# board.net
KiCad netlist of a schematic drawn in EAGLE
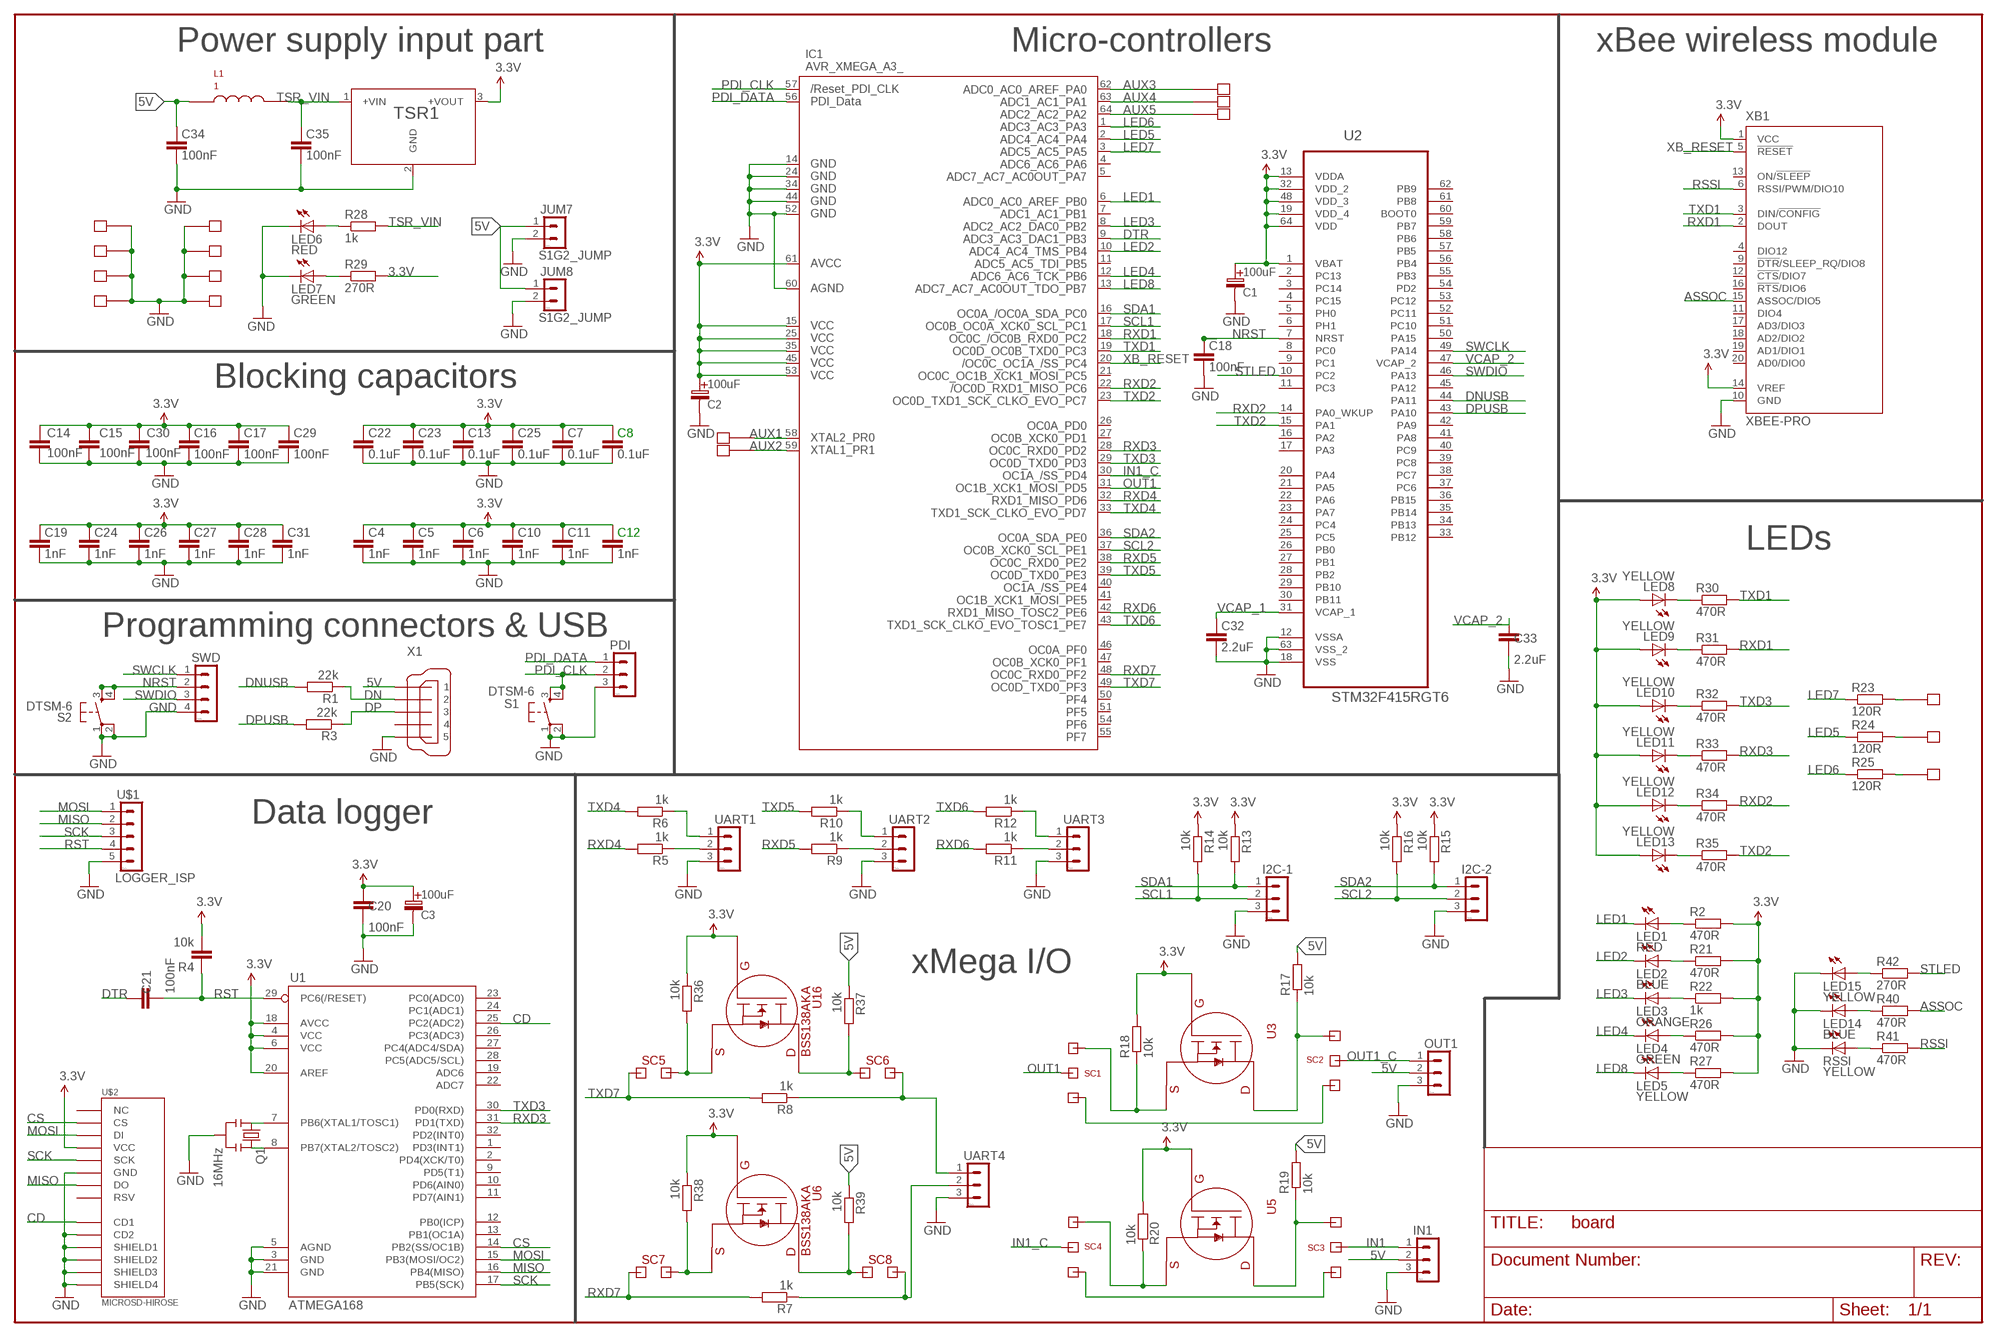
[diagram p0: schematic, sheet 1]

(export (version "E")
  (design (tool "Eeschema 10.0.6"))
  (components
    (comp (ref "AUX1")
      (value "PIN")
      (footprint "eagle-import:PIN")
      (libsource (lib "eagle-import") (part "PIN"))
    )
    (comp (ref "AUX2")
      (value "PIN")
      (footprint "eagle-import:PIN")
      (libsource (lib "eagle-import") (part "PIN"))
    )
    (comp (ref "AUX3")
      (value "PIN")
      (footprint "eagle-import:PIN")
      (libsource (lib "eagle-import") (part "PIN"))
    )
    (comp (ref "AUX4")
      (value "PIN")
      (footprint "eagle-import:PIN")
      (libsource (lib "eagle-import") (part "PIN"))
    )
    (comp (ref "AUX5")
      (value "PIN")
      (footprint "eagle-import:PIN")
      (libsource (lib "eagle-import") (part "PIN"))
    )
    (comp (ref "C1")
      (value "100uF")
      (footprint "eagle-import:B")
      (libsource (lib "eagle-import") (part "CAPACITOR_TANTAL"))
    )
    (comp (ref "C2")
      (value "100uF")
      (footprint "eagle-import:B")
      (libsource (lib "eagle-import") (part "CAPACITOR_TANTAL"))
    )
    (comp (ref "C3")
      (value "100uF")
      (footprint "eagle-import:B")
      (libsource (lib "eagle-import") (part "CAPACITOR_TANTAL"))
    )
    (comp (ref "C4")
      (value "1nF")
      (footprint "eagle-import:C0805")
      (libsource (lib "eagle-import") (part "C-EUC0805"))
    )
    (comp (ref "C5")
      (value "1nF")
      (footprint "eagle-import:C0805")
      (libsource (lib "eagle-import") (part "C-EUC0805"))
    )
    (comp (ref "C6")
      (value "1nF")
      (footprint "eagle-import:C0805")
      (libsource (lib "eagle-import") (part "C-EUC0805"))
    )
    (comp (ref "C7")
      (value "0.1uF")
      (footprint "eagle-import:C0805")
      (libsource (lib "eagle-import") (part "C-EUC0805"))
    )
    (comp (ref "C8")
      (value "0.1uF")
      (footprint "eagle-import:C0805")
      (libsource (lib "eagle-import") (part "C-EUC0805"))
    )
    (comp (ref "C10")
      (value "1nF")
      (footprint "eagle-import:C0805")
      (libsource (lib "eagle-import") (part "C-EUC0805"))
    )
    (comp (ref "C11")
      (value "1nF")
      (footprint "eagle-import:C0805")
      (libsource (lib "eagle-import") (part "C-EUC0805"))
    )
    (comp (ref "C12")
      (value "1nF")
      (footprint "eagle-import:C0805")
      (libsource (lib "eagle-import") (part "C-EUC0805"))
    )
    (comp (ref "C13")
      (value "0.1uF")
      (footprint "eagle-import:C0805")
      (libsource (lib "eagle-import") (part "C-EUC0805"))
    )
    (comp (ref "C14")
      (value "100nF")
      (footprint "eagle-import:C0805")
      (libsource (lib "eagle-import") (part "C-EUC0805"))
    )
    (comp (ref "C15")
      (value "100nF")
      (footprint "eagle-import:C0805")
      (libsource (lib "eagle-import") (part "C-EUC0805"))
    )
    (comp (ref "C16")
      (value "100nF")
      (footprint "eagle-import:C0805")
      (libsource (lib "eagle-import") (part "C-EUC0805"))
    )
    (comp (ref "C17")
      (value "100nF")
      (footprint "eagle-import:C0805")
      (libsource (lib "eagle-import") (part "C-EUC0805"))
    )
    (comp (ref "C18")
      (value "100nF")
      (footprint "eagle-import:C0805")
      (libsource (lib "eagle-import") (part "C-EUC0805"))
    )
    (comp (ref "C19")
      (value "1nF")
      (footprint "eagle-import:C0805")
      (libsource (lib "eagle-import") (part "C-EUC0805"))
    )
    (comp (ref "C20")
      (value "100nF")
      (footprint "eagle-import:C0805")
      (libsource (lib "eagle-import") (part "C-EUC0805"))
    )
    (comp (ref "C21")
      (value "100nF")
      (footprint "eagle-import:C0805")
      (libsource (lib "eagle-import") (part "C-EUC0805"))
    )
    (comp (ref "C22")
      (value "0.1uF")
      (footprint "eagle-import:C0805")
      (libsource (lib "eagle-import") (part "C-EUC0805"))
    )
    (comp (ref "C23")
      (value "0.1uF")
      (footprint "eagle-import:C0805")
      (libsource (lib "eagle-import") (part "C-EUC0805"))
    )
    (comp (ref "C24")
      (value "1nF")
      (footprint "eagle-import:C0805")
      (libsource (lib "eagle-import") (part "C-EUC0805"))
    )
    (comp (ref "C25")
      (value "0.1uF")
      (footprint "eagle-import:C0805")
      (libsource (lib "eagle-import") (part "C-EUC0805"))
    )
    (comp (ref "C26")
      (value "1nF")
      (footprint "eagle-import:C0805")
      (libsource (lib "eagle-import") (part "C-EUC0805"))
    )
    (comp (ref "C27")
      (value "1nF")
      (footprint "eagle-import:C0805")
      (libsource (lib "eagle-import") (part "C-EUC0805"))
    )
    (comp (ref "C28")
      (value "1nF")
      (footprint "eagle-import:C0805")
      (libsource (lib "eagle-import") (part "C-EUC0805"))
    )
    (comp (ref "C29")
      (value "100nF")
      (footprint "eagle-import:C0805")
      (libsource (lib "eagle-import") (part "C-EUC0805"))
    )
    (comp (ref "C30")
      (value "100nF")
      (footprint "eagle-import:C0805")
      (libsource (lib "eagle-import") (part "C-EUC0805"))
    )
    (comp (ref "C31")
      (value "1nF")
      (footprint "eagle-import:C0805")
      (libsource (lib "eagle-import") (part "C-EUC0805"))
    )
    (comp (ref "C32")
      (value "2.2uF")
      (footprint "eagle-import:C0805")
      (libsource (lib "eagle-import") (part "C-EUC0805"))
    )
    (comp (ref "C33")
      (value "2.2uF")
      (footprint "eagle-import:C0805")
      (libsource (lib "eagle-import") (part "C-EUC0805"))
    )
    (comp (ref "C34")
      (value "100nF")
      (footprint "eagle-import:C0805")
      (libsource (lib "eagle-import") (part "C-EUC0805"))
    )
    (comp (ref "C35")
      (value "100nF")
      (footprint "eagle-import:C0805")
      (libsource (lib "eagle-import") (part "C-EUC0805"))
    )
    (comp (ref "I2C-1")
      (value "S1G3_JUMP")
      (footprint "eagle-import:S1G3_JUM")
      (libsource (lib "eagle-import") (part "S1G3_JUMP"))
    )
    (comp (ref "I2C-2")
      (value "S1G3_JUMP")
      (footprint "eagle-import:S1G3_JUM")
      (libsource (lib "eagle-import") (part "S1G3_JUMP"))
    )
    (comp (ref "IC1")
      (value "AVR_XMEGA_A3_")
      (footprint "eagle-import:TQFP64")
      (libsource (lib "eagle-import") (part "AVR_XMEGA_A3_"))
    )
    (comp (ref "IN1")
      (value "S1G3_JUMP")
      (footprint "eagle-import:S1G3_JUM")
      (libsource (lib "eagle-import") (part "S1G3_JUMP"))
    )
    (comp (ref "JUM7")
      (value "S1G2_JUMP")
      (footprint "eagle-import:S1G2_JUM")
      (libsource (lib "eagle-import") (part "S1G2_JUMP"))
    )
    (comp (ref "JUM8")
      (value "S1G2_JUMP")
      (footprint "eagle-import:S1G2_JUM")
      (libsource (lib "eagle-import") (part "S1G2_JUMP"))
    )
    (comp (ref "L1")
      (value "1")
      (footprint "eagle-import:SDR0604")
      (libsource (lib "eagle-import") (part "LSDR0604"))
    )
    (comp (ref "LED1")
      (value "RED")
      (footprint "eagle-import:SML0805")
      (libsource (lib "eagle-import") (part "LEDSML0805"))
    )
    (comp (ref "LED2")
      (value "BLUE")
      (footprint "eagle-import:SML0805")
      (libsource (lib "eagle-import") (part "LEDSML0805"))
    )
    (comp (ref "LED3")
      (value "ORANGE")
      (footprint "eagle-import:SML0805")
      (libsource (lib "eagle-import") (part "LEDSML0805"))
    )
    (comp (ref "LED4")
      (value "GREEN")
      (footprint "eagle-import:SML0805")
      (libsource (lib "eagle-import") (part "LEDSML0805"))
    )
    (comp (ref "LED5")
      (value "YELLOW")
      (footprint "eagle-import:SML0805")
      (libsource (lib "eagle-import") (part "LEDSML0805"))
    )
    (comp (ref "LED6")
      (value "RED")
      (footprint "eagle-import:SML0805")
      (libsource (lib "eagle-import") (part "LEDSML0805"))
    )
    (comp (ref "LED7")
      (value "GREEN")
      (footprint "eagle-import:SML0805")
      (libsource (lib "eagle-import") (part "LEDSML0805"))
    )
    (comp (ref "LED8")
      (value "YELLOW")
      (footprint "eagle-import:SML0805")
      (libsource (lib "eagle-import") (part "LEDSML0805"))
    )
    (comp (ref "LED9")
      (value "YELLOW")
      (footprint "eagle-import:SML0805")
      (libsource (lib "eagle-import") (part "LEDSML0805"))
    )
    (comp (ref "LED10")
      (value "YELLOW")
      (footprint "eagle-import:SML0805")
      (libsource (lib "eagle-import") (part "LEDSML0805"))
    )
    (comp (ref "LED11")
      (value "YELLOW")
      (footprint "eagle-import:SML0805")
      (libsource (lib "eagle-import") (part "LEDSML0805"))
    )
    (comp (ref "LED12")
      (value "YELLOW")
      (footprint "eagle-import:SML0805")
      (libsource (lib "eagle-import") (part "LEDSML0805"))
    )
    (comp (ref "LED13")
      (value "YELLOW")
      (footprint "eagle-import:SML0805")
      (libsource (lib "eagle-import") (part "LEDSML0805"))
    )
    (comp (ref "LED14")
      (value "BLUE")
      (footprint "eagle-import:SML0805")
      (libsource (lib "eagle-import") (part "LEDSML0805"))
    )
    (comp (ref "LED15")
      (value "YELLOW")
      (footprint "eagle-import:SML0805")
      (libsource (lib "eagle-import") (part "LEDSML0805"))
    )
    (comp (ref "OUT1")
      (value "S1G3_JUMP")
      (footprint "eagle-import:S1G3_JUM")
      (libsource (lib "eagle-import") (part "S1G3_JUMP"))
    )
    (comp (ref "PDI")
      (value "S1G3_JUMP")
      (footprint "eagle-import:S1G3_JUM")
      (libsource (lib "eagle-import") (part "S1G3_JUMP"))
    )
    (comp (ref "Q1")
      (value "16MHz")
      (footprint "eagle-import:RESONATOR-SMD")
      (libsource (lib "eagle-import") (part "RESONATORSMD"))
    )
    (comp (ref "R1")
      (value "22k")
      (footprint "eagle-import:R0805")
      (libsource (lib "eagle-import") (part "R-EU_R0805"))
    )
    (comp (ref "R2")
      (value "470R")
      (footprint "eagle-import:R0805")
      (libsource (lib "eagle-import") (part "R-EU_R0805"))
    )
    (comp (ref "R3")
      (value "22k")
      (footprint "eagle-import:R0805")
      (libsource (lib "eagle-import") (part "R-EU_R0805"))
    )
    (comp (ref "R4")
      (value "10k")
      (footprint "eagle-import:C0805")
      (libsource (lib "eagle-import") (part "C-EUC0805"))
    )
    (comp (ref "R5")
      (value "1k")
      (footprint "eagle-import:R0805")
      (libsource (lib "eagle-import") (part "R-EU_R0805"))
    )
    (comp (ref "R6")
      (value "1k")
      (footprint "eagle-import:R0805")
      (libsource (lib "eagle-import") (part "R-EU_R0805"))
    )
    (comp (ref "R7")
      (value "1k")
      (footprint "eagle-import:R0805")
      (libsource (lib "eagle-import") (part "R-EU_R0805"))
    )
    (comp (ref "R8")
      (value "1k")
      (footprint "eagle-import:R0805")
      (libsource (lib "eagle-import") (part "R-EU_R0805"))
    )
    (comp (ref "R9")
      (value "1k")
      (footprint "eagle-import:R0805")
      (libsource (lib "eagle-import") (part "R-EU_R0805"))
    )
    (comp (ref "R10")
      (value "1k")
      (footprint "eagle-import:R0805")
      (libsource (lib "eagle-import") (part "R-EU_R0805"))
    )
    (comp (ref "R11")
      (value "1k")
      (footprint "eagle-import:R0805")
      (libsource (lib "eagle-import") (part "R-EU_R0805"))
    )
    (comp (ref "R12")
      (value "1k")
      (footprint "eagle-import:R0805")
      (libsource (lib "eagle-import") (part "R-EU_R0805"))
    )
    (comp (ref "R13")
      (value "10k")
      (footprint "eagle-import:R0805")
      (libsource (lib "eagle-import") (part "R-EU_R0805"))
    )
    (comp (ref "R14")
      (value "10k")
      (footprint "eagle-import:R0805")
      (libsource (lib "eagle-import") (part "R-EU_R0805"))
    )
    (comp (ref "R15")
      (value "10k")
      (footprint "eagle-import:R0805")
      (libsource (lib "eagle-import") (part "R-EU_R0805"))
    )
    (comp (ref "R16")
      (value "10k")
      (footprint "eagle-import:R0805")
      (libsource (lib "eagle-import") (part "R-EU_R0805"))
    )
    (comp (ref "R17")
      (value "10k")
      (footprint "eagle-import:R0805")
      (libsource (lib "eagle-import") (part "R-EU_R0805"))
    )
    (comp (ref "R18")
      (value "10k")
      (footprint "eagle-import:R0805")
      (libsource (lib "eagle-import") (part "R-EU_R0805"))
    )
    (comp (ref "R19")
      (value "10k")
      (footprint "eagle-import:R0805")
      (libsource (lib "eagle-import") (part "R-EU_R0805"))
    )
    (comp (ref "R20")
      (value "10k")
      (footprint "eagle-import:R0805")
      (libsource (lib "eagle-import") (part "R-EU_R0805"))
    )
    (comp (ref "R21")
      (value "470R")
      (footprint "eagle-import:R0805")
      (libsource (lib "eagle-import") (part "R-EU_R0805"))
    )
    (comp (ref "R22")
      (value "1k")
      (footprint "eagle-import:R0805")
      (libsource (lib "eagle-import") (part "R-EU_R0805"))
    )
    (comp (ref "R23")
      (value "120R")
      (footprint "eagle-import:R0805")
      (libsource (lib "eagle-import") (part "R-EU_R0805"))
    )
    (comp (ref "R24")
      (value "120R")
      (footprint "eagle-import:R0805")
      (libsource (lib "eagle-import") (part "R-EU_R0805"))
    )
    (comp (ref "R25")
      (value "120R")
      (footprint "eagle-import:R0805")
      (libsource (lib "eagle-import") (part "R-EU_R0805"))
    )
    (comp (ref "R26")
      (value "470R")
      (footprint "eagle-import:R0805")
      (libsource (lib "eagle-import") (part "R-EU_R0805"))
    )
    (comp (ref "R27")
      (value "470R")
      (footprint "eagle-import:R0805")
      (libsource (lib "eagle-import") (part "R-EU_R0805"))
    )
    (comp (ref "R28")
      (value "1k")
      (footprint "eagle-import:R0805")
      (libsource (lib "eagle-import") (part "R-EU_R0805"))
    )
    (comp (ref "R29")
      (value "270R")
      (footprint "eagle-import:R0805")
      (libsource (lib "eagle-import") (part "R-EU_R0805"))
    )
    (comp (ref "R30")
      (value "470R")
      (footprint "eagle-import:R0805")
      (libsource (lib "eagle-import") (part "R-EU_R0805"))
    )
    (comp (ref "R31")
      (value "470R")
      (footprint "eagle-import:R0805")
      (libsource (lib "eagle-import") (part "R-EU_R0805"))
    )
    (comp (ref "R32")
      (value "470R")
      (footprint "eagle-import:R0805")
      (libsource (lib "eagle-import") (part "R-EU_R0805"))
    )
    (comp (ref "R33")
      (value "470R")
      (footprint "eagle-import:R0805")
      (libsource (lib "eagle-import") (part "R-EU_R0805"))
    )
    (comp (ref "R34")
      (value "470R")
      (footprint "eagle-import:R0805")
      (libsource (lib "eagle-import") (part "R-EU_R0805"))
    )
    (comp (ref "R35")
      (value "470R")
      (footprint "eagle-import:R0805")
      (libsource (lib "eagle-import") (part "R-EU_R0805"))
    )
    (comp (ref "R36")
      (value "10k")
      (footprint "eagle-import:R0805")
      (libsource (lib "eagle-import") (part "R-EU_R0805"))
    )
    (comp (ref "R37")
      (value "10k")
      (footprint "eagle-import:R0805")
      (libsource (lib "eagle-import") (part "R-EU_R0805"))
    )
    (comp (ref "R38")
      (value "10k")
      (footprint "eagle-import:R0805")
      (libsource (lib "eagle-import") (part "R-EU_R0805"))
    )
    (comp (ref "R39")
      (value "10k")
      (footprint "eagle-import:R0805")
      (libsource (lib "eagle-import") (part "R-EU_R0805"))
    )
    (comp (ref "R40")
      (value "470R")
      (footprint "eagle-import:R0805")
      (libsource (lib "eagle-import") (part "R-EU_R0805"))
    )
    (comp (ref "R41")
      (value "470R")
      (footprint "eagle-import:R0805")
      (libsource (lib "eagle-import") (part "R-EU_R0805"))
    )
    (comp (ref "R42")
      (value "270R")
      (footprint "eagle-import:R0805")
      (libsource (lib "eagle-import") (part "R-EU_R0805"))
    )
    (comp (ref "RSSI")
      (value "YELLOW")
      (footprint "eagle-import:SML0805")
      (libsource (lib "eagle-import") (part "LEDSML0805"))
    )
    (comp (ref "S1")
      (value "DTSM-6")
      (footprint "eagle-import:DTSM-6")
      (libsource (lib "eagle-import") (part "DTSM-6"))
    )
    (comp (ref "S2")
      (value "DTSM-6")
      (footprint "eagle-import:DTSM-6")
      (libsource (lib "eagle-import") (part "DTSM-6"))
    )
    (comp (ref "SC1")
      (value "SOLDER_SWITCH_ONE")
      (footprint "eagle-import:SOLDER_SWITCH")
      (libsource (lib "eagle-import") (part "SOLDER_SWITCH_ONE"))
    )
    (comp (ref "SC2")
      (value "SOLDER_SWITCH_TWO")
      (footprint "eagle-import:SOLDER_SWITCH")
      (libsource (lib "eagle-import") (part "SOLDER_SWITCH_TWO"))
    )
    (comp (ref "SC3")
      (value "SOLDER_SWITCH_ONE")
      (footprint "eagle-import:SOLDER_SWITCH")
      (libsource (lib "eagle-import") (part "SOLDER_SWITCH_ONE"))
    )
    (comp (ref "SC4")
      (value "SOLDER_SWITCH_TWO")
      (footprint "eagle-import:SOLDER_SWITCH")
      (libsource (lib "eagle-import") (part "SOLDER_SWITCH_TWO"))
    )
    (comp (ref "SC5")
      (value "SOLDER_SWITCH_2")
      (footprint "eagle-import:SOLDER_SWITCH_2")
      (libsource (lib "eagle-import") (part "SOLDER_SWITCH_2"))
    )
    (comp (ref "SC6")
      (value "SOLDER_SWITCH_2")
      (footprint "eagle-import:SOLDER_SWITCH_2")
      (libsource (lib "eagle-import") (part "SOLDER_SWITCH_2"))
    )
    (comp (ref "SC7")
      (value "SOLDER_SWITCH_2")
      (footprint "eagle-import:SOLDER_SWITCH_2")
      (libsource (lib "eagle-import") (part "SOLDER_SWITCH_2"))
    )
    (comp (ref "SC8")
      (value "SOLDER_SWITCH_2")
      (footprint "eagle-import:SOLDER_SWITCH_2")
      (libsource (lib "eagle-import") (part "SOLDER_SWITCH_2"))
    )
    (comp (ref "SWD")
      (value "S1G4_JUMP_SQUARE")
      (footprint "eagle-import:2X02")
      (libsource (lib "eagle-import") (part "S1G4_JUMP_SQUARE"))
    )
    (comp (ref "TSR")
      (value "TSR1")
      (footprint "eagle-import:TSR1")
      (libsource (lib "eagle-import") (part "TSR1"))
    )
    (comp (ref "U$1")
      (value "LOGGER_ISP")
      (footprint "eagle-import:LOGGER_ISP")
      (libsource (lib "eagle-import") (part "LOGGER_ISP"))
    )
    (comp (ref "U$2")
      (value "MICROSD-HIROSE")
      (footprint "eagle-import:MICROSD_HOLDER-HIROSE-DM3AT")
      (libsource (lib "eagle-import") (part "MICROSD-HIROSE"))
    )
    (comp (ref "U$10")
      (value "PIN")
      (footprint "eagle-import:PIN")
      (libsource (lib "eagle-import") (part "PIN"))
    )
    (comp (ref "U$11")
      (value "PIN")
      (footprint "eagle-import:PIN")
      (libsource (lib "eagle-import") (part "PIN"))
    )
    (comp (ref "U$12")
      (value "PIN")
      (footprint "eagle-import:PIN")
      (libsource (lib "eagle-import") (part "PIN"))
    )
    (comp (ref "U$15")
      (value "PIN")
      (footprint "eagle-import:PIN")
      (libsource (lib "eagle-import") (part "PIN"))
    )
    (comp (ref "U$16")
      (value "PIN")
      (footprint "eagle-import:PIN")
      (libsource (lib "eagle-import") (part "PIN"))
    )
    (comp (ref "U$17")
      (value "PIN")
      (footprint "eagle-import:PIN")
      (libsource (lib "eagle-import") (part "PIN"))
    )
    (comp (ref "U$18")
      (value "PIN")
      (footprint "eagle-import:PIN")
      (libsource (lib "eagle-import") (part "PIN"))
    )
    (comp (ref "U$19")
      (value "PIN")
      (footprint "eagle-import:PIN")
      (libsource (lib "eagle-import") (part "PIN"))
    )
    (comp (ref "U$20")
      (value "PIN")
      (footprint "eagle-import:PIN")
      (libsource (lib "eagle-import") (part "PIN"))
    )
    (comp (ref "U$21")
      (value "PIN")
      (footprint "eagle-import:PIN")
      (libsource (lib "eagle-import") (part "PIN"))
    )
    (comp (ref "U$22")
      (value "PIN")
      (footprint "eagle-import:PIN")
      (libsource (lib "eagle-import") (part "PIN"))
    )
    (comp (ref "U1")
      (value "ATMEGA168")
      (footprint "eagle-import:TQFP32-08")
      (libsource (lib "eagle-import") (part "ATMEGA168"))
    )
    (comp (ref "U2")
      (value "STM32F415RGT6")
      (footprint "eagle-import:QFP50P1200X1200X160-64N")
      (libsource (lib "eagle-import") (part "STM32F415RGT6"))
    )
    (comp (ref "U3")
      (value "BSS138AKA")
      (footprint "eagle-import:SOT-23")
      (libsource (lib "eagle-import") (part "BSS138AKA"))
    )
    (comp (ref "U5")
      (value "BSS138AKA")
      (footprint "eagle-import:SOT-23")
      (libsource (lib "eagle-import") (part "BSS138AKA"))
    )
    (comp (ref "U6")
      (value "BSS138AKA")
      (footprint "eagle-import:SOT-23")
      (libsource (lib "eagle-import") (part "medipix_BSS138AKA"))
    )
    (comp (ref "U16")
      (value "BSS138AKA")
      (footprint "eagle-import:SOT-23")
      (libsource (lib "eagle-import") (part "medipix_BSS138AKA"))
    )
    (comp (ref "UART1")
      (value "S1G3_JUMP")
      (footprint "eagle-import:S1G3_JUM")
      (libsource (lib "eagle-import") (part "S1G3_JUMP"))
    )
    (comp (ref "UART2")
      (value "S1G3_JUMP")
      (footprint "eagle-import:S1G3_JUM")
      (libsource (lib "eagle-import") (part "S1G3_JUMP"))
    )
    (comp (ref "UART3")
      (value "S1G3_JUMP")
      (footprint "eagle-import:S1G3_JUM")
      (libsource (lib "eagle-import") (part "S1G3_JUMP"))
    )
    (comp (ref "UART4")
      (value "S1G3_JUMP")
      (footprint "eagle-import:S1G3_JUM")
      (libsource (lib "eagle-import") (part "S1G3_JUMP"))
    )
    (comp (ref "X1")
      (value "MINI-USB-UX60A-MB-5ST")
      (footprint "eagle-import:UX60A-MB-5ST")
      (libsource (lib "eagle-import") (part "MINI-USB-UX60A-MB-5ST"))
    )
    (comp (ref "XB1")
      (value "XBEE-PRO")
      (footprint "eagle-import:XBEE-PRO")
      (fields (field (name "MPN") "XBP24-AWI-001"))
      (libsource (lib "eagle-import") (part "XBEE-PRO"))
    )
  )
  (nets
    (net (code "1") (name "/ASSOC") (class "Default")
      (node (ref "R40") (pin "2") (pinfunction "2_2") (pintype "passive"))
      (node (ref "XB1") (pin "15") (pinfunction "ASSOC/DIO5_15") (pintype "bidirectional"))
    )
    (net (code "2") (name "/AUX1") (class "Default")
      (node (ref "AUX1") (pin "P$1") (pinfunction "D_P$1") (pintype "bidirectional"))
      (node (ref "IC1") (pin "58") (pinfunction "PR0_58") (pintype "bidirectional"))
    )
    (net (code "3") (name "/AUX2") (class "Default")
      (node (ref "AUX2") (pin "P$1") (pinfunction "D_P$1") (pintype "bidirectional"))
      (node (ref "IC1") (pin "59") (pinfunction "PR1_59") (pintype "bidirectional"))
    )
    (net (code "4") (name "/AUX3") (class "Default")
      (node (ref "AUX3") (pin "P$1") (pinfunction "D_P$1") (pintype "bidirectional"))
      (node (ref "IC1") (pin "62") (pinfunction "PA0_62") (pintype "bidirectional"))
    )
    (net (code "5") (name "/AUX4") (class "Default")
      (node (ref "AUX4") (pin "P$1") (pinfunction "D_P$1") (pintype "bidirectional"))
      (node (ref "IC1") (pin "63") (pinfunction "PA1_63") (pintype "bidirectional"))
    )
    (net (code "6") (name "/AUX5") (class "Default")
      (node (ref "AUX5") (pin "P$1") (pinfunction "D_P$1") (pintype "bidirectional"))
      (node (ref "IC1") (pin "64") (pinfunction "PA2_64") (pintype "bidirectional"))
    )
    (net (code "7") (name "/CD") (class "Default")
      (node (ref "U$2") (pin "CD1") (pinfunction "CD1_CD1") (pintype "bidirectional"))
      (node (ref "U1") (pin "25") (pinfunction "PC2(ADC2)_25") (pintype "bidirectional"))
    )
    (net (code "8") (name "/CS") (class "Default")
      (node (ref "U$2") (pin "DAT3") (pinfunction "CS_DAT3") (pintype "bidirectional"))
      (node (ref "U1") (pin "14") (pinfunction "PB2(SS/OC1B)_14") (pintype "bidirectional"))
    )
    (net (code "9") (name "/DN") (class "Default")
      (node (ref "R1") (pin "1") (pinfunction "1_1") (pintype "passive"))
      (node (ref "X1") (pin "2") (pinfunction "2_2") (pintype "input"))
    )
    (net (code "10") (name "/DNUSB") (class "Default")
      (node (ref "R1") (pin "2") (pinfunction "2_2") (pintype "passive"))
      (node (ref "U2") (pin "44") (pinfunction "PA11_44") (pintype "bidirectional"))
    )
    (net (code "11") (name "/DP") (class "Default")
      (node (ref "R3") (pin "1") (pinfunction "1_1") (pintype "passive"))
      (node (ref "X1") (pin "3") (pinfunction "3_3") (pintype "input"))
    )
    (net (code "12") (name "/DPUSB") (class "Default")
      (node (ref "R3") (pin "2") (pinfunction "2_2") (pintype "passive"))
      (node (ref "U2") (pin "43") (pinfunction "PA10_43") (pintype "bidirectional"))
    )
    (net (code "13") (name "/DTR") (class "Default")
      (node (ref "C21") (pin "2") (pinfunction "2_2") (pintype "passive"))
      (node (ref "IC1") (pin "9") (pinfunction "PB3_9") (pintype "bidirectional"))
    )
    (net (code "14") (name "/IN1") (class "Default")
      (node (ref "IN1") (pin "1") (pinfunction "1_1") (pintype "passive"))
      (node (ref "SC3") (pin "MID") (pinfunction "MID_MID") (pintype "bidirectional"))
    )
    (net (code "15") (name "/IN1_C") (class "Default")
      (node (ref "IC1") (pin "30") (pinfunction "PD4_30") (pintype "bidirectional"))
      (node (ref "SC4") (pin "MID") (pinfunction "MID_MID") (pintype "bidirectional"))
    )
    (net (code "16") (name "/LED1") (class "Default")
      (node (ref "IC1") (pin "6") (pinfunction "PB0_6") (pintype "bidirectional"))
      (node (ref "LED1") (pin "C") (pinfunction "C_C") (pintype "passive"))
    )
    (net (code "17") (name "/LED2") (class "Default")
      (node (ref "IC1") (pin "10") (pinfunction "PB4_10") (pintype "bidirectional"))
      (node (ref "LED2") (pin "C") (pinfunction "C_C") (pintype "passive"))
    )
    (net (code "18") (name "/LED3") (class "Default")
      (node (ref "IC1") (pin "8") (pinfunction "PB2_8") (pintype "bidirectional"))
      (node (ref "LED3") (pin "C") (pinfunction "C_C") (pintype "passive"))
    )
    (net (code "19") (name "/LED4") (class "Default")
      (node (ref "IC1") (pin "12") (pinfunction "PB6_12") (pintype "bidirectional"))
      (node (ref "LED4") (pin "C") (pinfunction "C_C") (pintype "passive"))
    )
    (net (code "20") (name "/LED5") (class "Default")
      (node (ref "IC1") (pin "2") (pinfunction "PA4_2") (pintype "bidirectional"))
      (node (ref "R24") (pin "1") (pinfunction "1_1") (pintype "passive"))
    )
    (net (code "21") (name "/LED6") (class "Default")
      (node (ref "IC1") (pin "1") (pinfunction "PA3_1") (pintype "bidirectional"))
      (node (ref "R25") (pin "1") (pinfunction "1_1") (pintype "passive"))
    )
    (net (code "22") (name "/LED7") (class "Default")
      (node (ref "IC1") (pin "3") (pinfunction "PA5_3") (pintype "bidirectional"))
      (node (ref "R23") (pin "1") (pinfunction "1_1") (pintype "passive"))
    )
    (net (code "23") (name "/LED8") (class "Default")
      (node (ref "IC1") (pin "13") (pinfunction "PB7_13") (pintype "bidirectional"))
      (node (ref "LED5") (pin "C") (pinfunction "C_C") (pintype "passive"))
    )
    (net (code "24") (name "/MISO") (class "Default")
      (node (ref "U$1") (pin "2") (pinfunction "2_2") (pintype "passive"))
      (node (ref "U$2") (pin "DAT0") (pinfunction "DO_DAT0") (pintype "bidirectional"))
      (node (ref "U1") (pin "16") (pinfunction "PB4(MISO)_16") (pintype "bidirectional"))
    )
    (net (code "25") (name "/MOSI") (class "Default")
      (node (ref "U$1") (pin "1") (pinfunction "1_1") (pintype "passive"))
      (node (ref "U$2") (pin "CMD") (pinfunction "DI_CMD") (pintype "bidirectional"))
      (node (ref "U1") (pin "15") (pinfunction "PB3(MOSI/OC2)_15") (pintype "bidirectional"))
    )
    (net (code "26") (name "/NRST") (class "Default")
      (node (ref "C18") (pin "2") (pinfunction "2_2") (pintype "passive"))
      (node (ref "S2") (pin "3") (pinfunction "3_3") (pintype "passive"))
      (node (ref "S2") (pin "4") (pinfunction "4_4") (pintype "passive"))
      (node (ref "SWD") (pin "2") (pinfunction "2_2") (pintype "passive"))
      (node (ref "U2") (pin "7") (pinfunction "NRST_7") (pintype "passive"))
    )
    (net (code "27") (name "/OUT1") (class "Default")
      (node (ref "IC1") (pin "31") (pinfunction "PD5_31") (pintype "bidirectional"))
      (node (ref "SC1") (pin "MID") (pinfunction "MID_MID") (pintype "bidirectional"))
    )
    (net (code "28") (name "/OUT1_C") (class "Default")
      (node (ref "OUT1") (pin "1") (pinfunction "1_1") (pintype "passive"))
      (node (ref "SC2") (pin "MID") (pinfunction "MID_MID") (pintype "bidirectional"))
    )
    (net (code "29") (name "/PDI_CLK") (class "Default")
      (node (ref "IC1") (pin "57") (pinfunction "RESET_57") (pintype "bidirectional"))
      (node (ref "PDI") (pin "2") (pinfunction "2_2") (pintype "passive"))
      (node (ref "S1") (pin "3") (pinfunction "3_3") (pintype "passive"))
      (node (ref "S1") (pin "4") (pinfunction "4_4") (pintype "passive"))
    )
    (net (code "30") (name "/PDI_DATA") (class "Default")
      (node (ref "IC1") (pin "56") (pinfunction "PDI_DATA_56") (pintype "bidirectional"))
      (node (ref "PDI") (pin "1") (pinfunction "1_1") (pintype "passive"))
    )
    (net (code "31") (name "/RSSI") (class "Default")
      (node (ref "R41") (pin "2") (pinfunction "2_2") (pintype "passive"))
      (node (ref "XB1") (pin "6") (pinfunction "RSSI/PWM/DIO10_6") (pintype "output"))
    )
    (net (code "32") (name "/RST") (class "Default")
      (node (ref "C21") (pin "1") (pinfunction "1_1") (pintype "passive"))
      (node (ref "R4") (pin "1") (pinfunction "1_1") (pintype "passive"))
      (node (ref "U$1") (pin "4") (pinfunction "4_4") (pintype "passive"))
      (node (ref "U1") (pin "29") (pinfunction "PC6(/RESET)_29") (pintype "bidirectional"))
    )
    (net (code "33") (name "/RXD1") (class "Default")
      (node (ref "IC1") (pin "18") (pinfunction "PC2_18") (pintype "bidirectional"))
      (node (ref "R31") (pin "2") (pinfunction "2_2") (pintype "passive"))
      (node (ref "XB1") (pin "2") (pinfunction "DOUT_2") (pintype "output"))
    )
    (net (code "34") (name "/RXD2") (class "Default")
      (node (ref "IC1") (pin "22") (pinfunction "PC6_22") (pintype "bidirectional"))
      (node (ref "R34") (pin "2") (pinfunction "2_2") (pintype "passive"))
      (node (ref "U2") (pin "14") (pinfunction "PA0_WKUP_14") (pintype "passive"))
    )
    (net (code "35") (name "/RXD3") (class "Default")
      (node (ref "IC1") (pin "28") (pinfunction "PD2_28") (pintype "bidirectional"))
      (node (ref "R33") (pin "2") (pinfunction "2_2") (pintype "passive"))
      (node (ref "U1") (pin "31") (pinfunction "PD1(TXD)_31") (pintype "bidirectional"))
    )
    (net (code "36") (name "/RXD4") (class "Default")
      (node (ref "IC1") (pin "32") (pinfunction "PD6_32") (pintype "bidirectional"))
      (node (ref "R5") (pin "2") (pinfunction "2_2") (pintype "passive"))
    )
    (net (code "37") (name "/RXD5") (class "Default")
      (node (ref "IC1") (pin "38") (pinfunction "PE2_38") (pintype "bidirectional"))
      (node (ref "R9") (pin "2") (pinfunction "2_2") (pintype "passive"))
    )
    (net (code "38") (name "/RXD6") (class "Default")
      (node (ref "IC1") (pin "42") (pinfunction "PE6_42") (pintype "bidirectional"))
      (node (ref "R11") (pin "2") (pinfunction "2_2") (pintype "passive"))
    )
    (net (code "39") (name "/RXD7") (class "Default")
      (node (ref "IC1") (pin "48") (pinfunction "PF2_48") (pintype "bidirectional"))
      (node (ref "R7") (pin "2") (pinfunction "2_2") (pintype "passive"))
      (node (ref "SC7") (pin "MID") (pinfunction "MID_MID") (pintype "bidirectional"))
    )
    (net (code "40") (name "/SCK") (class "Default")
      (node (ref "U$1") (pin "3") (pinfunction "3_3") (pintype "passive"))
      (node (ref "U$2") (pin "CLK") (pinfunction "SCK_CLK") (pintype "bidirectional"))
      (node (ref "U1") (pin "17") (pinfunction "PB5(SCK)_17") (pintype "bidirectional"))
    )
    (net (code "41") (name "/SCL1") (class "Default")
      (node (ref "I2C-1") (pin "2") (pinfunction "2_2") (pintype "passive"))
      (node (ref "IC1") (pin "17") (pinfunction "PC1_17") (pintype "bidirectional"))
      (node (ref "R14") (pin "2") (pinfunction "2_2") (pintype "passive"))
    )
    (net (code "42") (name "/SCL2") (class "Default")
      (node (ref "I2C-2") (pin "2") (pinfunction "2_2") (pintype "passive"))
      (node (ref "IC1") (pin "37") (pinfunction "PE1_37") (pintype "bidirectional"))
      (node (ref "R16") (pin "2") (pinfunction "2_2") (pintype "passive"))
    )
    (net (code "43") (name "/SDA1") (class "Default")
      (node (ref "I2C-1") (pin "1") (pinfunction "1_1") (pintype "passive"))
      (node (ref "IC1") (pin "16") (pinfunction "PC0_16") (pintype "bidirectional"))
      (node (ref "R13") (pin "2") (pinfunction "2_2") (pintype "passive"))
    )
    (net (code "44") (name "/SDA2") (class "Default")
      (node (ref "I2C-2") (pin "1") (pinfunction "1_1") (pintype "passive"))
      (node (ref "IC1") (pin "36") (pinfunction "PE0_36") (pintype "bidirectional"))
      (node (ref "R15") (pin "2") (pinfunction "2_2") (pintype "passive"))
    )
    (net (code "45") (name "/STLED") (class "Default")
      (node (ref "R42") (pin "2") (pinfunction "2_2") (pintype "passive"))
      (node (ref "U2") (pin "10") (pinfunction "PC2_10") (pintype "bidirectional"))
    )
    (net (code "46") (name "/SWCLK") (class "Default")
      (node (ref "SWD") (pin "1") (pinfunction "1_1") (pintype "passive"))
      (node (ref "U2") (pin "49") (pinfunction "PA14_49") (pintype "bidirectional"))
    )
    (net (code "47") (name "/SWDIO") (class "Default")
      (node (ref "SWD") (pin "3") (pinfunction "3_3") (pintype "passive"))
      (node (ref "U2") (pin "46") (pinfunction "PA13_46") (pintype "bidirectional"))
    )
    (net (code "48") (name "/TSR_VIN") (class "Default")
      (node (ref "C35") (pin "2") (pinfunction "2_2") (pintype "passive"))
      (node (ref "L1") (pin "P$2") (pinfunction "P$2_P$2") (pintype "bidirectional"))
      (node (ref "R28") (pin "2") (pinfunction "2_2") (pintype "passive"))
      (node (ref "TSR") (pin "1") (pinfunction "+VIN_1") (pintype "bidirectional"))
    )
    (net (code "49") (name "/TXD1") (class "Default")
      (node (ref "IC1") (pin "19") (pinfunction "PC3_19") (pintype "bidirectional"))
      (node (ref "R30") (pin "2") (pinfunction "2_2") (pintype "passive"))
      (node (ref "XB1") (pin "3") (pinfunction "DIN/~{CONFIG}_3") (pintype "input"))
    )
    (net (code "50") (name "/TXD2") (class "Default")
      (node (ref "IC1") (pin "23") (pinfunction "PC7_23") (pintype "bidirectional"))
      (node (ref "R35") (pin "2") (pinfunction "2_2") (pintype "passive"))
      (node (ref "U2") (pin "15") (pinfunction "PA1_15") (pintype "bidirectional"))
    )
    (net (code "51") (name "/TXD3") (class "Default")
      (node (ref "IC1") (pin "29") (pinfunction "PD3_29") (pintype "bidirectional"))
      (node (ref "R32") (pin "2") (pinfunction "2_2") (pintype "passive"))
      (node (ref "U1") (pin "30") (pinfunction "PD0(RXD)_30") (pintype "bidirectional"))
    )
    (net (code "52") (name "/TXD4") (class "Default")
      (node (ref "IC1") (pin "33") (pinfunction "PD7_33") (pintype "bidirectional"))
      (node (ref "R6") (pin "2") (pinfunction "2_2") (pintype "passive"))
    )
    (net (code "53") (name "/TXD5") (class "Default")
      (node (ref "IC1") (pin "39") (pinfunction "PE3_39") (pintype "bidirectional"))
      (node (ref "R10") (pin "2") (pinfunction "2_2") (pintype "passive"))
    )
    (net (code "54") (name "/TXD6") (class "Default")
      (node (ref "IC1") (pin "43") (pinfunction "PE7_43") (pintype "bidirectional"))
      (node (ref "R12") (pin "2") (pinfunction "2_2") (pintype "passive"))
    )
    (net (code "55") (name "/TXD7") (class "Default")
      (node (ref "IC1") (pin "49") (pinfunction "PF3_49") (pintype "bidirectional"))
      (node (ref "R8") (pin "2") (pinfunction "2_2") (pintype "passive"))
      (node (ref "SC5") (pin "MID") (pinfunction "MID_MID") (pintype "bidirectional"))
    )
    (net (code "56") (name "/VCAP_1") (class "Default")
      (node (ref "C32") (pin "2") (pinfunction "2_2") (pintype "passive"))
      (node (ref "U2") (pin "31") (pinfunction "VCAP_1_31") (pintype "passive"))
    )
    (net (code "57") (name "/VCAP_2") (class "Default")
      (node (ref "C33") (pin "2") (pinfunction "2_2") (pintype "passive"))
      (node (ref "U2") (pin "47") (pinfunction "VCAP_2_47") (pintype "passive"))
    )
    (net (code "58") (name "/XB_RESET") (class "Default")
      (node (ref "IC1") (pin "20") (pinfunction "PC4_20") (pintype "bidirectional"))
      (node (ref "XB1") (pin "5") (pinfunction "~{RESET}_5") (pintype "input"))
    )
    (net (code "59") (name "3.3V") (class "Default")
      (node (ref "C1") (pin "+") (pinfunction "C_EL+_+") (pintype "passive"))
      (node (ref "C10") (pin "2") (pinfunction "2_2") (pintype "passive"))
      (node (ref "C11") (pin "2") (pinfunction "2_2") (pintype "passive"))
      (node (ref "C12") (pin "2") (pinfunction "2_2") (pintype "passive"))
      (node (ref "C13") (pin "2") (pinfunction "2_2") (pintype "passive"))
      (node (ref "C14") (pin "2") (pinfunction "2_2") (pintype "passive"))
      (node (ref "C15") (pin "2") (pinfunction "2_2") (pintype "passive"))
      (node (ref "C16") (pin "2") (pinfunction "2_2") (pintype "passive"))
      (node (ref "C17") (pin "2") (pinfunction "2_2") (pintype "passive"))
      (node (ref "C19") (pin "2") (pinfunction "2_2") (pintype "passive"))
      (node (ref "C2") (pin "+") (pinfunction "C_EL+_+") (pintype "passive"))
      (node (ref "C20") (pin "2") (pinfunction "2_2") (pintype "passive"))
      (node (ref "C22") (pin "2") (pinfunction "2_2") (pintype "passive"))
      (node (ref "C23") (pin "2") (pinfunction "2_2") (pintype "passive"))
      (node (ref "C24") (pin "2") (pinfunction "2_2") (pintype "passive"))
      (node (ref "C25") (pin "2") (pinfunction "2_2") (pintype "passive"))
      (node (ref "C26") (pin "2") (pinfunction "2_2") (pintype "passive"))
      (node (ref "C27") (pin "2") (pinfunction "2_2") (pintype "passive"))
      (node (ref "C28") (pin "2") (pinfunction "2_2") (pintype "passive"))
      (node (ref "C29") (pin "2") (pinfunction "2_2") (pintype "passive"))
      (node (ref "C3") (pin "+") (pinfunction "C_EL+_+") (pintype "passive"))
      (node (ref "C30") (pin "2") (pinfunction "2_2") (pintype "passive"))
      (node (ref "C31") (pin "2") (pinfunction "2_2") (pintype "passive"))
      (node (ref "C4") (pin "2") (pinfunction "2_2") (pintype "passive"))
      (node (ref "C5") (pin "2") (pinfunction "2_2") (pintype "passive"))
      (node (ref "C6") (pin "2") (pinfunction "2_2") (pintype "passive"))
      (node (ref "C7") (pin "2") (pinfunction "2_2") (pintype "passive"))
      (node (ref "C8") (pin "2") (pinfunction "2_2") (pintype "passive"))
      (node (ref "IC1") (pin "15") (pinfunction "VCC1_15") (pintype "bidirectional"))
      (node (ref "IC1") (pin "25") (pinfunction "VCC2_25") (pintype "bidirectional"))
      (node (ref "IC1") (pin "35") (pinfunction "VCC3_35") (pintype "bidirectional"))
      (node (ref "IC1") (pin "45") (pinfunction "VCC4_45") (pintype "bidirectional"))
      (node (ref "IC1") (pin "53") (pinfunction "VCC5_53") (pintype "bidirectional"))
      (node (ref "IC1") (pin "61") (pinfunction "AVCC_61") (pintype "bidirectional"))
      (node (ref "LED10") (pin "A") (pinfunction "A_A") (pintype "passive"))
      (node (ref "LED11") (pin "A") (pinfunction "A_A") (pintype "passive"))
      (node (ref "LED12") (pin "A") (pinfunction "A_A") (pintype "passive"))
      (node (ref "LED13") (pin "A") (pinfunction "A_A") (pintype "passive"))
      (node (ref "LED8") (pin "A") (pinfunction "A_A") (pintype "passive"))
      (node (ref "LED9") (pin "A") (pinfunction "A_A") (pintype "passive"))
      (node (ref "R13") (pin "1") (pinfunction "1_1") (pintype "passive"))
      (node (ref "R14") (pin "1") (pinfunction "1_1") (pintype "passive"))
      (node (ref "R15") (pin "1") (pinfunction "1_1") (pintype "passive"))
      (node (ref "R16") (pin "1") (pinfunction "1_1") (pintype "passive"))
      (node (ref "R18") (pin "2") (pinfunction "2_2") (pintype "passive"))
      (node (ref "R2") (pin "2") (pinfunction "2_2") (pintype "passive"))
      (node (ref "R20") (pin "2") (pinfunction "2_2") (pintype "passive"))
      (node (ref "R21") (pin "2") (pinfunction "2_2") (pintype "passive"))
      (node (ref "R22") (pin "2") (pinfunction "2_2") (pintype "passive"))
      (node (ref "R26") (pin "2") (pinfunction "2_2") (pintype "passive"))
      (node (ref "R27") (pin "2") (pinfunction "2_2") (pintype "passive"))
      (node (ref "R29") (pin "2") (pinfunction "2_2") (pintype "passive"))
      (node (ref "R36") (pin "1") (pinfunction "1_1") (pintype "passive"))
      (node (ref "R38") (pin "1") (pinfunction "1_1") (pintype "passive"))
      (node (ref "R4") (pin "2") (pinfunction "2_2") (pintype "passive"))
      (node (ref "TSR") (pin "3") (pinfunction "+VOUT_3") (pintype "bidirectional"))
      (node (ref "U$2") (pin "VDD") (pinfunction "VCC_VDD") (pintype "power_in"))
      (node (ref "U1") (pin "18") (pinfunction "AVCC_18") (pintype "bidirectional"))
      (node (ref "U1") (pin "20") (pinfunction "AREF_20") (pintype "bidirectional"))
      (node (ref "U1") (pin "4") (pinfunction "VCC_4") (pintype "bidirectional"))
      (node (ref "U1") (pin "6") (pinfunction "VCC_6") (pintype "bidirectional"))
      (node (ref "U16") (pin "1") (pinfunction "G_1") (pintype "passive"))
      (node (ref "U2") (pin "1") (pinfunction "VBAT_1") (pintype "passive"))
      (node (ref "U2") (pin "13") (pinfunction "VDDA_13") (pintype "power_in"))
      (node (ref "U2") (pin "19") (pinfunction "VDD_4_19") (pintype "power_in"))
      (node (ref "U2") (pin "32") (pinfunction "VDD_2_32") (pintype "power_in"))
      (node (ref "U2") (pin "48") (pinfunction "VDD_3_48") (pintype "power_in"))
      (node (ref "U2") (pin "64") (pinfunction "VDD_64") (pintype "power_in"))
      (node (ref "U3") (pin "1") (pinfunction "G_1") (pintype "passive"))
      (node (ref "U5") (pin "1") (pinfunction "G_1") (pintype "passive"))
      (node (ref "U6") (pin "1") (pinfunction "G_1") (pintype "passive"))
      (node (ref "XB1") (pin "1") (pinfunction "VCC_1") (pintype "power_in"))
      (node (ref "XB1") (pin "14") (pinfunction "VREF_14") (pintype "input"))
    )
    (net (code "60") (name "5V") (class "Default")
      (node (ref "C34") (pin "2") (pinfunction "2_2") (pintype "passive"))
      (node (ref "IN1") (pin "2") (pinfunction "2_2") (pintype "passive"))
      (node (ref "JUM7") (pin "1") (pinfunction "1_1") (pintype "passive"))
      (node (ref "JUM8") (pin "1") (pinfunction "1_1") (pintype "passive"))
      (node (ref "L1") (pin "P$1") (pinfunction "P$1_P$1") (pintype "bidirectional"))
      (node (ref "OUT1") (pin "2") (pinfunction "2_2") (pintype "passive"))
      (node (ref "R17") (pin "2") (pinfunction "2_2") (pintype "passive"))
      (node (ref "R19") (pin "2") (pinfunction "2_2") (pintype "passive"))
      (node (ref "R37") (pin "1") (pinfunction "1_1") (pintype "passive"))
      (node (ref "R39") (pin "1") (pinfunction "1_1") (pintype "passive"))
      (node (ref "X1") (pin "1") (pinfunction "1_1") (pintype "input"))
    )
    (net (code "61") (name "GND") (class "Default")
      (node (ref "C1") (pin "-") (pinfunction "C_EL-_-") (pintype "passive"))
      (node (ref "C10") (pin "1") (pinfunction "1_1") (pintype "passive"))
      (node (ref "C11") (pin "1") (pinfunction "1_1") (pintype "passive"))
      (node (ref "C12") (pin "1") (pinfunction "1_1") (pintype "passive"))
      (node (ref "C13") (pin "1") (pinfunction "1_1") (pintype "passive"))
      (node (ref "C14") (pin "1") (pinfunction "1_1") (pintype "passive"))
      (node (ref "C15") (pin "1") (pinfunction "1_1") (pintype "passive"))
      (node (ref "C16") (pin "1") (pinfunction "1_1") (pintype "passive"))
      (node (ref "C17") (pin "1") (pinfunction "1_1") (pintype "passive"))
      (node (ref "C18") (pin "1") (pinfunction "1_1") (pintype "passive"))
      (node (ref "C19") (pin "1") (pinfunction "1_1") (pintype "passive"))
      (node (ref "C2") (pin "-") (pinfunction "C_EL-_-") (pintype "passive"))
      (node (ref "C20") (pin "1") (pinfunction "1_1") (pintype "passive"))
      (node (ref "C22") (pin "1") (pinfunction "1_1") (pintype "passive"))
      (node (ref "C23") (pin "1") (pinfunction "1_1") (pintype "passive"))
      (node (ref "C24") (pin "1") (pinfunction "1_1") (pintype "passive"))
      (node (ref "C25") (pin "1") (pinfunction "1_1") (pintype "passive"))
      (node (ref "C26") (pin "1") (pinfunction "1_1") (pintype "passive"))
      (node (ref "C27") (pin "1") (pinfunction "1_1") (pintype "passive"))
      (node (ref "C28") (pin "1") (pinfunction "1_1") (pintype "passive"))
      (node (ref "C29") (pin "1") (pinfunction "1_1") (pintype "passive"))
      (node (ref "C3") (pin "-") (pinfunction "C_EL-_-") (pintype "passive"))
      (node (ref "C30") (pin "1") (pinfunction "1_1") (pintype "passive"))
      (node (ref "C31") (pin "1") (pinfunction "1_1") (pintype "passive"))
      (node (ref "C32") (pin "1") (pinfunction "1_1") (pintype "passive"))
      (node (ref "C33") (pin "1") (pinfunction "1_1") (pintype "passive"))
      (node (ref "C34") (pin "1") (pinfunction "1_1") (pintype "passive"))
      (node (ref "C35") (pin "1") (pinfunction "1_1") (pintype "passive"))
      (node (ref "C4") (pin "1") (pinfunction "1_1") (pintype "passive"))
      (node (ref "C5") (pin "1") (pinfunction "1_1") (pintype "passive"))
      (node (ref "C6") (pin "1") (pinfunction "1_1") (pintype "passive"))
      (node (ref "C7") (pin "1") (pinfunction "1_1") (pintype "passive"))
      (node (ref "C8") (pin "1") (pinfunction "1_1") (pintype "passive"))
      (node (ref "I2C-1") (pin "3") (pinfunction "3_3") (pintype "passive"))
      (node (ref "I2C-2") (pin "3") (pinfunction "3_3") (pintype "passive"))
      (node (ref "IC1") (pin "14") (pinfunction "GND1_14") (pintype "bidirectional"))
      (node (ref "IC1") (pin "24") (pinfunction "GND2_24") (pintype "bidirectional"))
      (node (ref "IC1") (pin "34") (pinfunction "GND3_34") (pintype "bidirectional"))
      (node (ref "IC1") (pin "44") (pinfunction "GND4_44") (pintype "bidirectional"))
      (node (ref "IC1") (pin "52") (pinfunction "GND5_52") (pintype "bidirectional"))
      (node (ref "IC1") (pin "60") (pinfunction "AGND_60") (pintype "bidirectional"))
      (node (ref "IN1") (pin "3") (pinfunction "3_3") (pintype "passive"))
      (node (ref "JUM7") (pin "2") (pinfunction "2_2") (pintype "passive"))
      (node (ref "JUM8") (pin "2") (pinfunction "2_2") (pintype "passive"))
      (node (ref "LED14") (pin "C") (pinfunction "C_C") (pintype "passive"))
      (node (ref "LED15") (pin "C") (pinfunction "C_C") (pintype "passive"))
      (node (ref "LED6") (pin "C") (pinfunction "C_C") (pintype "passive"))
      (node (ref "LED7") (pin "C") (pinfunction "C_C") (pintype "passive"))
      (node (ref "OUT1") (pin "3") (pinfunction "3_3") (pintype "passive"))
      (node (ref "PDI") (pin "3") (pinfunction "3_3") (pintype "passive"))
      (node (ref "Q1") (pin "2") (pinfunction "2_2") (pintype "passive"))
      (node (ref "RSSI") (pin "C") (pinfunction "C_C") (pintype "passive"))
      (node (ref "S1") (pin "1") (pinfunction "1_1") (pintype "passive"))
      (node (ref "S1") (pin "2") (pinfunction "2_2") (pintype "passive"))
      (node (ref "S2") (pin "1") (pinfunction "1_1") (pintype "passive"))
      (node (ref "S2") (pin "2") (pinfunction "2_2") (pintype "passive"))
      (node (ref "SWD") (pin "4") (pinfunction "4_4") (pintype "passive"))
      (node (ref "TSR") (pin "2") (pinfunction "GND_2") (pintype "bidirectional"))
      (node (ref "U$1") (pin "5") (pinfunction "5_5") (pintype "passive"))
      (node (ref "U$15") (pin "P$1") (pinfunction "D_P$1") (pintype "bidirectional"))
      (node (ref "U$16") (pin "P$1") (pinfunction "D_P$1") (pintype "bidirectional"))
      (node (ref "U$17") (pin "P$1") (pinfunction "D_P$1") (pintype "bidirectional"))
      (node (ref "U$18") (pin "P$1") (pinfunction "D_P$1") (pintype "bidirectional"))
      (node (ref "U$19") (pin "P$1") (pinfunction "D_P$1") (pintype "bidirectional"))
      (node (ref "U$2") (pin "BODY1") (pinfunction "SHIELD1_BODY1") (pintype "bidirectional"))
      (node (ref "U$2") (pin "BODY2") (pinfunction "SHIELD2_BODY2") (pintype "bidirectional"))
      (node (ref "U$2") (pin "BODY3") (pinfunction "SHIELD3_BODY3") (pintype "bidirectional"))
      (node (ref "U$2") (pin "BODY4") (pinfunction "SHIELD4_BODY4") (pintype "bidirectional"))
      (node (ref "U$2") (pin "CD2") (pinfunction "CD2_CD2") (pintype "bidirectional"))
      (node (ref "U$2") (pin "VSS") (pinfunction "GND_VSS") (pintype "power_in"))
      (node (ref "U$20") (pin "P$1") (pinfunction "D_P$1") (pintype "bidirectional"))
      (node (ref "U$21") (pin "P$1") (pinfunction "D_P$1") (pintype "bidirectional"))
      (node (ref "U$22") (pin "P$1") (pinfunction "D_P$1") (pintype "bidirectional"))
      (node (ref "U1") (pin "21") (pinfunction "GND_21") (pintype "bidirectional"))
      (node (ref "U1") (pin "3") (pinfunction "GND_3") (pintype "bidirectional"))
      (node (ref "U1") (pin "5") (pinfunction "AGND_5") (pintype "bidirectional"))
      (node (ref "U2") (pin "12") (pinfunction "VSSA_12") (pintype "power_in"))
      (node (ref "U2") (pin "18") (pinfunction "VSS_18") (pintype "power_in"))
      (node (ref "U2") (pin "63") (pinfunction "VSS_2_63") (pintype "power_in"))
      (node (ref "UART1") (pin "3") (pinfunction "3_3") (pintype "passive"))
      (node (ref "UART2") (pin "3") (pinfunction "3_3") (pintype "passive"))
      (node (ref "UART3") (pin "3") (pinfunction "3_3") (pintype "passive"))
      (node (ref "UART4") (pin "3") (pinfunction "3_3") (pintype "passive"))
      (node (ref "X1") (pin "5") (pinfunction "5_5") (pintype "input"))
      (node (ref "XB1") (pin "10") (pinfunction "GND_10") (pintype "power_in"))
    )
    (net (code "62") (name "Net-(LED1-PadA)") (class "Default")
      (node (ref "LED1") (pin "A") (pinfunction "A_A") (pintype "passive"))
      (node (ref "R2") (pin "1") (pinfunction "1_1") (pintype "passive"))
    )
    (net (code "63") (name "Net-(LED2-PadA)") (class "Default")
      (node (ref "LED2") (pin "A") (pinfunction "A_A") (pintype "passive"))
      (node (ref "R21") (pin "1") (pinfunction "1_1") (pintype "passive"))
    )
    (net (code "64") (name "Net-(LED3-PadA)") (class "Default")
      (node (ref "LED3") (pin "A") (pinfunction "A_A") (pintype "passive"))
      (node (ref "R22") (pin "1") (pinfunction "1_1") (pintype "passive"))
    )
    (net (code "65") (name "Net-(LED4-PadA)") (class "Default")
      (node (ref "LED4") (pin "A") (pinfunction "A_A") (pintype "passive"))
      (node (ref "R26") (pin "1") (pinfunction "1_1") (pintype "passive"))
    )
    (net (code "66") (name "Net-(LED5-PadA)") (class "Default")
      (node (ref "LED5") (pin "A") (pinfunction "A_A") (pintype "passive"))
      (node (ref "R27") (pin "1") (pinfunction "1_1") (pintype "passive"))
    )
    (net (code "67") (name "Net-(LED6-PadA)") (class "Default")
      (node (ref "LED6") (pin "A") (pinfunction "A_A") (pintype "passive"))
      (node (ref "R28") (pin "1") (pinfunction "1_1") (pintype "passive"))
    )
    (net (code "68") (name "Net-(LED7-PadA)") (class "Default")
      (node (ref "LED7") (pin "A") (pinfunction "A_A") (pintype "passive"))
      (node (ref "R29") (pin "1") (pinfunction "1_1") (pintype "passive"))
    )
    (net (code "69") (name "Net-(LED8-PadC)") (class "Default")
      (node (ref "LED8") (pin "C") (pinfunction "C_C") (pintype "passive"))
      (node (ref "R30") (pin "1") (pinfunction "1_1") (pintype "passive"))
    )
    (net (code "70") (name "Net-(LED9-PadC)") (class "Default")
      (node (ref "LED9") (pin "C") (pinfunction "C_C") (pintype "passive"))
      (node (ref "R31") (pin "1") (pinfunction "1_1") (pintype "passive"))
    )
    (net (code "71") (name "Net-(LED10-PadC)") (class "Default")
      (node (ref "LED10") (pin "C") (pinfunction "C_C") (pintype "passive"))
      (node (ref "R32") (pin "1") (pinfunction "1_1") (pintype "passive"))
    )
    (net (code "72") (name "Net-(LED11-PadC)") (class "Default")
      (node (ref "LED11") (pin "C") (pinfunction "C_C") (pintype "passive"))
      (node (ref "R33") (pin "1") (pinfunction "1_1") (pintype "passive"))
    )
    (net (code "73") (name "Net-(LED12-PadC)") (class "Default")
      (node (ref "LED12") (pin "C") (pinfunction "C_C") (pintype "passive"))
      (node (ref "R34") (pin "1") (pinfunction "1_1") (pintype "passive"))
    )
    (net (code "74") (name "Net-(LED13-PadC)") (class "Default")
      (node (ref "LED13") (pin "C") (pinfunction "C_C") (pintype "passive"))
      (node (ref "R35") (pin "1") (pinfunction "1_1") (pintype "passive"))
    )
    (net (code "75") (name "Net-(LED14-PadA)") (class "Default")
      (node (ref "LED14") (pin "A") (pinfunction "A_A") (pintype "passive"))
      (node (ref "R40") (pin "1") (pinfunction "1_1") (pintype "passive"))
    )
    (net (code "76") (name "Net-(LED15-PadA)") (class "Default")
      (node (ref "LED15") (pin "A") (pinfunction "A_A") (pintype "passive"))
      (node (ref "R42") (pin "1") (pinfunction "1_1") (pintype "passive"))
    )
    (net (code "77") (name "Net-(R5-Pad1)") (class "Default")
      (node (ref "R5") (pin "1") (pinfunction "1_1") (pintype "passive"))
      (node (ref "UART1") (pin "2") (pinfunction "2_2") (pintype "passive"))
    )
    (net (code "78") (name "Net-(R6-Pad1)") (class "Default")
      (node (ref "R6") (pin "1") (pinfunction "1_1") (pintype "passive"))
      (node (ref "UART1") (pin "1") (pinfunction "1_1") (pintype "passive"))
    )
    (net (code "79") (name "Net-(R7-Pad1)") (class "Default")
      (node (ref "R7") (pin "1") (pinfunction "1_1") (pintype "passive"))
      (node (ref "SC8") (pin "1") (pinfunction "1_1") (pintype "bidirectional"))
      (node (ref "UART4") (pin "2") (pinfunction "2_2") (pintype "passive"))
    )
    (net (code "80") (name "Net-(R8-Pad1)") (class "Default")
      (node (ref "R8") (pin "1") (pinfunction "1_1") (pintype "passive"))
      (node (ref "SC6") (pin "1") (pinfunction "1_1") (pintype "bidirectional"))
      (node (ref "UART4") (pin "1") (pinfunction "1_1") (pintype "passive"))
    )
    (net (code "81") (name "Net-(R9-Pad1)") (class "Default")
      (node (ref "R9") (pin "1") (pinfunction "1_1") (pintype "passive"))
      (node (ref "UART2") (pin "2") (pinfunction "2_2") (pintype "passive"))
    )
    (net (code "82") (name "Net-(R10-Pad1)") (class "Default")
      (node (ref "R10") (pin "1") (pinfunction "1_1") (pintype "passive"))
      (node (ref "UART2") (pin "1") (pinfunction "1_1") (pintype "passive"))
    )
    (net (code "83") (name "Net-(R11-Pad1)") (class "Default")
      (node (ref "R11") (pin "1") (pinfunction "1_1") (pintype "passive"))
      (node (ref "UART3") (pin "2") (pinfunction "2_2") (pintype "passive"))
    )
    (net (code "84") (name "Net-(R12-Pad1)") (class "Default")
      (node (ref "R12") (pin "1") (pinfunction "1_1") (pintype "passive"))
      (node (ref "UART3") (pin "1") (pinfunction "1_1") (pintype "passive"))
    )
    (net (code "85") (name "Net-(R41-Pad1)") (class "Default")
      (node (ref "R41") (pin "1") (pinfunction "1_1") (pintype "passive"))
      (node (ref "RSSI") (pin "A") (pinfunction "A_A") (pintype "passive"))
    )
    (net (code "86") (name "Net-(SC2-1)") (class "Default")
      (node (ref "SC1") (pin "2") (pinfunction "2_2") (pintype "bidirectional"))
      (node (ref "SC2") (pin "2") (pinfunction "1_2") (pintype "bidirectional"))
    )
    (net (code "87") (name "Net-(SC2-2)") (class "Default")
      (node (ref "R17") (pin "1") (pinfunction "1_1") (pintype "passive"))
      (node (ref "SC2") (pin "1") (pinfunction "2_1") (pintype "bidirectional"))
      (node (ref "U3") (pin "3") (pinfunction "D_3") (pintype "passive"))
    )
    (net (code "88") (name "Net-(SC4-1)") (class "Default")
      (node (ref "SC3") (pin "2") (pinfunction "2_2") (pintype "bidirectional"))
      (node (ref "SC4") (pin "2") (pinfunction "1_2") (pintype "bidirectional"))
    )
    (net (code "89") (name "Net-(SC4-2)") (class "Default")
      (node (ref "R20") (pin "1") (pinfunction "1_1") (pintype "passive"))
      (node (ref "SC4") (pin "1") (pinfunction "2_1") (pintype "bidirectional"))
      (node (ref "U5") (pin "2") (pinfunction "S_2") (pintype "passive"))
    )
    (net (code "90") (name "Net-(U$10-D)") (class "Default")
      (node (ref "R23") (pin "2") (pinfunction "2_2") (pintype "passive"))
      (node (ref "U$10") (pin "P$1") (pinfunction "D_P$1") (pintype "bidirectional"))
    )
    (net (code "91") (name "Net-(U$11-D)") (class "Default")
      (node (ref "R24") (pin "2") (pinfunction "2_2") (pintype "passive"))
      (node (ref "U$11") (pin "P$1") (pinfunction "D_P$1") (pintype "bidirectional"))
    )
    (net (code "92") (name "Net-(U$12-D)") (class "Default")
      (node (ref "R25") (pin "2") (pinfunction "2_2") (pintype "passive"))
      (node (ref "U$12") (pin "P$1") (pinfunction "D_P$1") (pintype "bidirectional"))
    )
    (net (code "93") (name "Net-(U1-PB6(XTAL1{slash}TOSC1))") (class "Default")
      (node (ref "Q1") (pin "1") (pinfunction "1_1") (pintype "passive"))
      (node (ref "U1") (pin "7") (pinfunction "PB6(XTAL1/TOSC1)_7") (pintype "bidirectional"))
    )
    (net (code "94") (name "Net-(U1-PB7(XTAL2{slash}TOSC2))") (class "Default")
      (node (ref "Q1") (pin "3") (pinfunction "3_3") (pintype "passive"))
      (node (ref "U1") (pin "8") (pinfunction "PB7(XTAL2/TOSC2)_8") (pintype "bidirectional"))
    )
    (net (code "95") (name "Net-(U3-S)") (class "Default")
      (node (ref "R18") (pin "1") (pinfunction "1_1") (pintype "passive"))
      (node (ref "SC1") (pin "1") (pinfunction "1_1") (pintype "bidirectional"))
      (node (ref "U3") (pin "2") (pinfunction "S_2") (pintype "passive"))
    )
    (net (code "96") (name "Net-(U5-D)") (class "Default")
      (node (ref "R19") (pin "1") (pinfunction "1_1") (pintype "passive"))
      (node (ref "SC3") (pin "1") (pinfunction "1_1") (pintype "bidirectional"))
      (node (ref "U5") (pin "3") (pinfunction "D_3") (pintype "passive"))
    )
    (net (code "97") (name "Net-(U6-D)") (class "Default")
      (node (ref "R39") (pin "2") (pinfunction "2_2") (pintype "passive"))
      (node (ref "SC8") (pin "MID") (pinfunction "MID_MID") (pintype "bidirectional"))
      (node (ref "U6") (pin "3") (pinfunction "D_3") (pintype "passive"))
    )
    (net (code "98") (name "Net-(U6-S)") (class "Default")
      (node (ref "R38") (pin "2") (pinfunction "2_2") (pintype "passive"))
      (node (ref "SC7") (pin "1") (pinfunction "1_1") (pintype "bidirectional"))
      (node (ref "U6") (pin "2") (pinfunction "S_2") (pintype "passive"))
    )
    (net (code "99") (name "Net-(U16-D)") (class "Default")
      (node (ref "R37") (pin "2") (pinfunction "2_2") (pintype "passive"))
      (node (ref "SC6") (pin "MID") (pinfunction "MID_MID") (pintype "bidirectional"))
      (node (ref "U16") (pin "3") (pinfunction "D_3") (pintype "passive"))
    )
    (net (code "100") (name "Net-(U16-S)") (class "Default")
      (node (ref "R36") (pin "2") (pinfunction "2_2") (pintype "passive"))
      (node (ref "SC5") (pin "1") (pinfunction "1_1") (pintype "bidirectional"))
      (node (ref "U16") (pin "2") (pinfunction "S_2") (pintype "passive"))
    )
    (net (code "101") (name "unconnected-(IC1-PA6-Pad4)") (class "Default")
      (node (ref "IC1") (pin "4") (pinfunction "PA6_4") (pintype "bidirectional"))
    )
    (net (code "102") (name "unconnected-(IC1-PA7-Pad5)") (class "Default")
      (node (ref "IC1") (pin "5") (pinfunction "PA7_5") (pintype "bidirectional"))
    )
    (net (code "103") (name "unconnected-(IC1-PB1-Pad7)") (class "Default")
      (node (ref "IC1") (pin "7") (pinfunction "PB1_7") (pintype "bidirectional"))
    )
    (net (code "104") (name "unconnected-(IC1-PB5-Pad11)") (class "Default")
      (node (ref "IC1") (pin "11") (pinfunction "PB5_11") (pintype "bidirectional"))
    )
    (net (code "105") (name "unconnected-(IC1-PC5-Pad21)") (class "Default")
      (node (ref "IC1") (pin "21") (pinfunction "PC5_21") (pintype "bidirectional"))
    )
    (net (code "106") (name "unconnected-(IC1-PD0-Pad26)") (class "Default")
      (node (ref "IC1") (pin "26") (pinfunction "PD0_26") (pintype "bidirectional"))
    )
    (net (code "107") (name "unconnected-(IC1-PD1-Pad27)") (class "Default")
      (node (ref "IC1") (pin "27") (pinfunction "PD1_27") (pintype "bidirectional"))
    )
    (net (code "108") (name "unconnected-(IC1-PE4-Pad40)") (class "Default")
      (node (ref "IC1") (pin "40") (pinfunction "PE4_40") (pintype "bidirectional"))
    )
    (net (code "109") (name "unconnected-(IC1-PE5-Pad41)") (class "Default")
      (node (ref "IC1") (pin "41") (pinfunction "PE5_41") (pintype "bidirectional"))
    )
    (net (code "110") (name "unconnected-(IC1-PF0-Pad46)") (class "Default")
      (node (ref "IC1") (pin "46") (pinfunction "PF0_46") (pintype "bidirectional"))
    )
    (net (code "111") (name "unconnected-(IC1-PF1-Pad47)") (class "Default")
      (node (ref "IC1") (pin "47") (pinfunction "PF1_47") (pintype "bidirectional"))
    )
    (net (code "112") (name "unconnected-(IC1-PF4-Pad50)") (class "Default")
      (node (ref "IC1") (pin "50") (pinfunction "PF4_50") (pintype "bidirectional"))
    )
    (net (code "113") (name "unconnected-(IC1-PF5-Pad51)") (class "Default")
      (node (ref "IC1") (pin "51") (pinfunction "PF5_51") (pintype "bidirectional"))
    )
    (net (code "114") (name "unconnected-(IC1-PF6-Pad54)") (class "Default")
      (node (ref "IC1") (pin "54") (pinfunction "PF6_54") (pintype "bidirectional"))
    )
    (net (code "115") (name "unconnected-(IC1-PF7-Pad55)") (class "Default")
      (node (ref "IC1") (pin "55") (pinfunction "PF7_55") (pintype "bidirectional"))
    )
    (net (code "116") (name "unconnected-(U$2-NC-PadDAT2)") (class "Default")
      (node (ref "U$2") (pin "DAT2") (pinfunction "NC_DAT2") (pintype "bidirectional"))
    )
    (net (code "117") (name "unconnected-(U$2-RSV-PadDAT1)") (class "Default")
      (node (ref "U$2") (pin "DAT1") (pinfunction "RSV_DAT1") (pintype "bidirectional"))
    )
    (net (code "118") (name "unconnected-(U1-ADC6-Pad19)") (class "Default")
      (node (ref "U1") (pin "19") (pinfunction "ADC6_19") (pintype "bidirectional"))
    )
    (net (code "119") (name "unconnected-(U1-ADC7-Pad22)") (class "Default")
      (node (ref "U1") (pin "22") (pinfunction "ADC7_22") (pintype "bidirectional"))
    )
    (net (code "120") (name "unconnected-(U1-PB0(ICP)-Pad12)") (class "Default")
      (node (ref "U1") (pin "12") (pinfunction "PB0(ICP)_12") (pintype "bidirectional"))
    )
    (net (code "121") (name "unconnected-(U1-PB1(OC1A)-Pad13)") (class "Default")
      (node (ref "U1") (pin "13") (pinfunction "PB1(OC1A)_13") (pintype "bidirectional"))
    )
    (net (code "122") (name "unconnected-(U1-PC0(ADC0)-Pad23)") (class "Default")
      (node (ref "U1") (pin "23") (pinfunction "PC0(ADC0)_23") (pintype "bidirectional"))
    )
    (net (code "123") (name "unconnected-(U1-PC1(ADC1)-Pad24)") (class "Default")
      (node (ref "U1") (pin "24") (pinfunction "PC1(ADC1)_24") (pintype "bidirectional"))
    )
    (net (code "124") (name "unconnected-(U1-PC3(ADC3)-Pad26)") (class "Default")
      (node (ref "U1") (pin "26") (pinfunction "PC3(ADC3)_26") (pintype "bidirectional"))
    )
    (net (code "125") (name "unconnected-(U1-PC4(ADC4{slash}SDA)-Pad27)") (class "Default")
      (node (ref "U1") (pin "27") (pinfunction "PC4(ADC4/SDA)_27") (pintype "bidirectional"))
    )
    (net (code "126") (name "unconnected-(U1-PC5(ADC5{slash}SCL)-Pad28)") (class "Default")
      (node (ref "U1") (pin "28") (pinfunction "PC5(ADC5/SCL)_28") (pintype "bidirectional"))
    )
    (net (code "127") (name "unconnected-(U1-PD2(INT0)-Pad32)") (class "Default")
      (node (ref "U1") (pin "32") (pinfunction "PD2(INT0)_32") (pintype "bidirectional"))
    )
    (net (code "128") (name "unconnected-(U1-PD3(INT1)-Pad1)") (class "Default")
      (node (ref "U1") (pin "1") (pinfunction "PD3(INT1)_1") (pintype "bidirectional"))
    )
    (net (code "129") (name "unconnected-(U1-PD4(XCK{slash}T0)-Pad2)") (class "Default")
      (node (ref "U1") (pin "2") (pinfunction "PD4(XCK/T0)_2") (pintype "bidirectional"))
    )
    (net (code "130") (name "unconnected-(U1-PD5(T1)-Pad9)") (class "Default")
      (node (ref "U1") (pin "9") (pinfunction "PD5(T1)_9") (pintype "bidirectional"))
    )
    (net (code "131") (name "unconnected-(U1-PD6(AIN0)-Pad10)") (class "Default")
      (node (ref "U1") (pin "10") (pinfunction "PD6(AIN0)_10") (pintype "bidirectional"))
    )
    (net (code "132") (name "unconnected-(U1-PD7(AIN1)-Pad11)") (class "Default")
      (node (ref "U1") (pin "11") (pinfunction "PD7(AIN1)_11") (pintype "bidirectional"))
    )
    (net (code "133") (name "unconnected-(U2-BOOT0-Pad60)") (class "Default")
      (node (ref "U2") (pin "60") (pinfunction "BOOT0_60") (pintype "passive"))
    )
    (net (code "134") (name "unconnected-(U2-PA2-Pad16)") (class "Default")
      (node (ref "U2") (pin "16") (pinfunction "PA2_16") (pintype "bidirectional"))
    )
    (net (code "135") (name "unconnected-(U2-PA3-Pad17)") (class "Default")
      (node (ref "U2") (pin "17") (pinfunction "PA3_17") (pintype "bidirectional"))
    )
    (net (code "136") (name "unconnected-(U2-PA4-Pad20)") (class "Default")
      (node (ref "U2") (pin "20") (pinfunction "PA4_20") (pintype "bidirectional"))
    )
    (net (code "137") (name "unconnected-(U2-PA5-Pad21)") (class "Default")
      (node (ref "U2") (pin "21") (pinfunction "PA5_21") (pintype "bidirectional"))
    )
    (net (code "138") (name "unconnected-(U2-PA6-Pad22)") (class "Default")
      (node (ref "U2") (pin "22") (pinfunction "PA6_22") (pintype "bidirectional"))
    )
    (net (code "139") (name "unconnected-(U2-PA7-Pad23)") (class "Default")
      (node (ref "U2") (pin "23") (pinfunction "PA7_23") (pintype "bidirectional"))
    )
    (net (code "140") (name "unconnected-(U2-PA8-Pad41)") (class "Default")
      (node (ref "U2") (pin "41") (pinfunction "PA8_41") (pintype "bidirectional"))
    )
    (net (code "141") (name "unconnected-(U2-PA9-Pad42)") (class "Default")
      (node (ref "U2") (pin "42") (pinfunction "PA9_42") (pintype "bidirectional"))
    )
    (net (code "142") (name "unconnected-(U2-PA12-Pad45)") (class "Default")
      (node (ref "U2") (pin "45") (pinfunction "PA12_45") (pintype "bidirectional"))
    )
    (net (code "143") (name "unconnected-(U2-PA15-Pad50)") (class "Default")
      (node (ref "U2") (pin "50") (pinfunction "PA15_50") (pintype "bidirectional"))
    )
    (net (code "144") (name "unconnected-(U2-PB0-Pad26)") (class "Default")
      (node (ref "U2") (pin "26") (pinfunction "PB0_26") (pintype "bidirectional"))
    )
    (net (code "145") (name "unconnected-(U2-PB1-Pad27)") (class "Default")
      (node (ref "U2") (pin "27") (pinfunction "PB1_27") (pintype "bidirectional"))
    )
    (net (code "146") (name "unconnected-(U2-PB2-Pad28)") (class "Default")
      (node (ref "U2") (pin "28") (pinfunction "PB2_28") (pintype "bidirectional"))
    )
    (net (code "147") (name "unconnected-(U2-PB3-Pad55)") (class "Default")
      (node (ref "U2") (pin "55") (pinfunction "PB3_55") (pintype "bidirectional"))
    )
    (net (code "148") (name "unconnected-(U2-PB4-Pad56)") (class "Default")
      (node (ref "U2") (pin "56") (pinfunction "PB4_56") (pintype "bidirectional"))
    )
    (net (code "149") (name "unconnected-(U2-PB5-Pad57)") (class "Default")
      (node (ref "U2") (pin "57") (pinfunction "PB5_57") (pintype "bidirectional"))
    )
    (net (code "150") (name "unconnected-(U2-PB6-Pad58)") (class "Default")
      (node (ref "U2") (pin "58") (pinfunction "PB6_58") (pintype "bidirectional"))
    )
    (net (code "151") (name "unconnected-(U2-PB7-Pad59)") (class "Default")
      (node (ref "U2") (pin "59") (pinfunction "PB7_59") (pintype "bidirectional"))
    )
    (net (code "152") (name "unconnected-(U2-PB8-Pad61)") (class "Default")
      (node (ref "U2") (pin "61") (pinfunction "PB8_61") (pintype "bidirectional"))
    )
    (net (code "153") (name "unconnected-(U2-PB9-Pad62)") (class "Default")
      (node (ref "U2") (pin "62") (pinfunction "PB9_62") (pintype "bidirectional"))
    )
    (net (code "154") (name "unconnected-(U2-PB10-Pad29)") (class "Default")
      (node (ref "U2") (pin "29") (pinfunction "PB10_29") (pintype "bidirectional"))
    )
    (net (code "155") (name "unconnected-(U2-PB11-Pad30)") (class "Default")
      (node (ref "U2") (pin "30") (pinfunction "PB11_30") (pintype "bidirectional"))
    )
    (net (code "156") (name "unconnected-(U2-PB12-Pad33)") (class "Default")
      (node (ref "U2") (pin "33") (pinfunction "PB12_33") (pintype "bidirectional"))
    )
    (net (code "157") (name "unconnected-(U2-PB13-Pad34)") (class "Default")
      (node (ref "U2") (pin "34") (pinfunction "PB13_34") (pintype "bidirectional"))
    )
    (net (code "158") (name "unconnected-(U2-PB14-Pad35)") (class "Default")
      (node (ref "U2") (pin "35") (pinfunction "PB14_35") (pintype "bidirectional"))
    )
    (net (code "159") (name "unconnected-(U2-PB15-Pad36)") (class "Default")
      (node (ref "U2") (pin "36") (pinfunction "PB15_36") (pintype "bidirectional"))
    )
    (net (code "160") (name "unconnected-(U2-PC0-Pad8)") (class "Default")
      (node (ref "U2") (pin "8") (pinfunction "PC0_8") (pintype "bidirectional"))
    )
    (net (code "161") (name "unconnected-(U2-PC1-Pad9)") (class "Default")
      (node (ref "U2") (pin "9") (pinfunction "PC1_9") (pintype "bidirectional"))
    )
    (net (code "162") (name "unconnected-(U2-PC3-Pad11)") (class "Default")
      (node (ref "U2") (pin "11") (pinfunction "PC3_11") (pintype "bidirectional"))
    )
    (net (code "163") (name "unconnected-(U2-PC4-Pad24)") (class "Default")
      (node (ref "U2") (pin "24") (pinfunction "PC4_24") (pintype "bidirectional"))
    )
    (net (code "164") (name "unconnected-(U2-PC5-Pad25)") (class "Default")
      (node (ref "U2") (pin "25") (pinfunction "PC5_25") (pintype "bidirectional"))
    )
    (net (code "165") (name "unconnected-(U2-PC6-Pad37)") (class "Default")
      (node (ref "U2") (pin "37") (pinfunction "PC6_37") (pintype "bidirectional"))
    )
    (net (code "166") (name "unconnected-(U2-PC7-Pad38)") (class "Default")
      (node (ref "U2") (pin "38") (pinfunction "PC7_38") (pintype "bidirectional"))
    )
    (net (code "167") (name "unconnected-(U2-PC8-Pad39)") (class "Default")
      (node (ref "U2") (pin "39") (pinfunction "PC8_39") (pintype "bidirectional"))
    )
    (net (code "168") (name "unconnected-(U2-PC9-Pad40)") (class "Default")
      (node (ref "U2") (pin "40") (pinfunction "PC9_40") (pintype "bidirectional"))
    )
    (net (code "169") (name "unconnected-(U2-PC10-Pad51)") (class "Default")
      (node (ref "U2") (pin "51") (pinfunction "PC10_51") (pintype "bidirectional"))
    )
    (net (code "170") (name "unconnected-(U2-PC11-Pad52)") (class "Default")
      (node (ref "U2") (pin "52") (pinfunction "PC11_52") (pintype "bidirectional"))
    )
    (net (code "171") (name "unconnected-(U2-PC12-Pad53)") (class "Default")
      (node (ref "U2") (pin "53") (pinfunction "PC12_53") (pintype "bidirectional"))
    )
    (net (code "172") (name "unconnected-(U2-PC13-Pad2)") (class "Default")
      (node (ref "U2") (pin "2") (pinfunction "PC13_2") (pintype "bidirectional"))
    )
    (net (code "173") (name "unconnected-(U2-PC14-Pad3)") (class "Default")
      (node (ref "U2") (pin "3") (pinfunction "PC14_3") (pintype "bidirectional"))
    )
    (net (code "174") (name "unconnected-(U2-PC15-Pad4)") (class "Default")
      (node (ref "U2") (pin "4") (pinfunction "PC15_4") (pintype "bidirectional"))
    )
    (net (code "175") (name "unconnected-(U2-PD2-Pad54)") (class "Default")
      (node (ref "U2") (pin "54") (pinfunction "PD2_54") (pintype "bidirectional"))
    )
    (net (code "176") (name "unconnected-(U2-PH0-Pad5)") (class "Default")
      (node (ref "U2") (pin "5") (pinfunction "PH0_5") (pintype "bidirectional"))
    )
    (net (code "177") (name "unconnected-(U2-PH1-Pad6)") (class "Default")
      (node (ref "U2") (pin "6") (pinfunction "PH1_6") (pintype "bidirectional"))
    )
    (net (code "178") (name "unconnected-(X1-Pad4)") (class "Default")
      (node (ref "X1") (pin "4") (pinfunction "4_4") (pintype "input"))
    )
    (net (code "179") (name "unconnected-(XB1-AD0{slash}DIO0-Pad20)") (class "Default")
      (node (ref "XB1") (pin "20") (pinfunction "AD0/DIO0_20") (pintype "bidirectional"))
    )
    (net (code "180") (name "unconnected-(XB1-AD1{slash}DIO1-Pad19)") (class "Default")
      (node (ref "XB1") (pin "19") (pinfunction "AD1/DIO1_19") (pintype "bidirectional"))
    )
    (net (code "181") (name "unconnected-(XB1-AD2{slash}DIO2-Pad18)") (class "Default")
      (node (ref "XB1") (pin "18") (pinfunction "AD2/DIO2_18") (pintype "bidirectional"))
    )
    (net (code "182") (name "unconnected-(XB1-AD3{slash}DIO3-Pad17)") (class "Default")
      (node (ref "XB1") (pin "17") (pinfunction "AD3/DIO3_17") (pintype "bidirectional"))
    )
    (net (code "183") (name "unconnected-(XB1-DIO4-Pad11)") (class "Default")
      (node (ref "XB1") (pin "11") (pinfunction "DIO4_11") (pintype "bidirectional"))
    )
    (net (code "184") (name "unconnected-(XB1-DIO12-Pad4)") (class "Default")
      (node (ref "XB1") (pin "4") (pinfunction "DIO12_4") (pintype "bidirectional"))
    )
    (net (code "185") (name "unconnected-(XB1-ON{slash}~{SLEEP}-Pad13)") (class "Default")
      (node (ref "XB1") (pin "13") (pinfunction "ON/~{SLEEP}_13") (pintype "output"))
    )
    (net (code "186") (name "unconnected-(XB1-~{CTS}{slash}DIO7-Pad12)") (class "Default")
      (node (ref "XB1") (pin "12") (pinfunction "~{CTS}/DIO7_12") (pintype "bidirectional"))
    )
    (net (code "187") (name "unconnected-(XB1-~{DTR}{slash}SLEEP_RQ{slash}DIO8-Pad9)") (class "Default")
      (node (ref "XB1") (pin "9") (pinfunction "~{DTR}/SLEEP_RQ/DIO8_9") (pintype "bidirectional"))
    )
    (net (code "188") (name "unconnected-(XB1-~{RTS}{slash}DIO6-Pad16)") (class "Default")
      (node (ref "XB1") (pin "16") (pinfunction "~{RTS}/DIO6_16") (pintype "bidirectional"))
    )
  )
)
